# scope.net
KiCad netlist of a schematic drawn in EAGLE
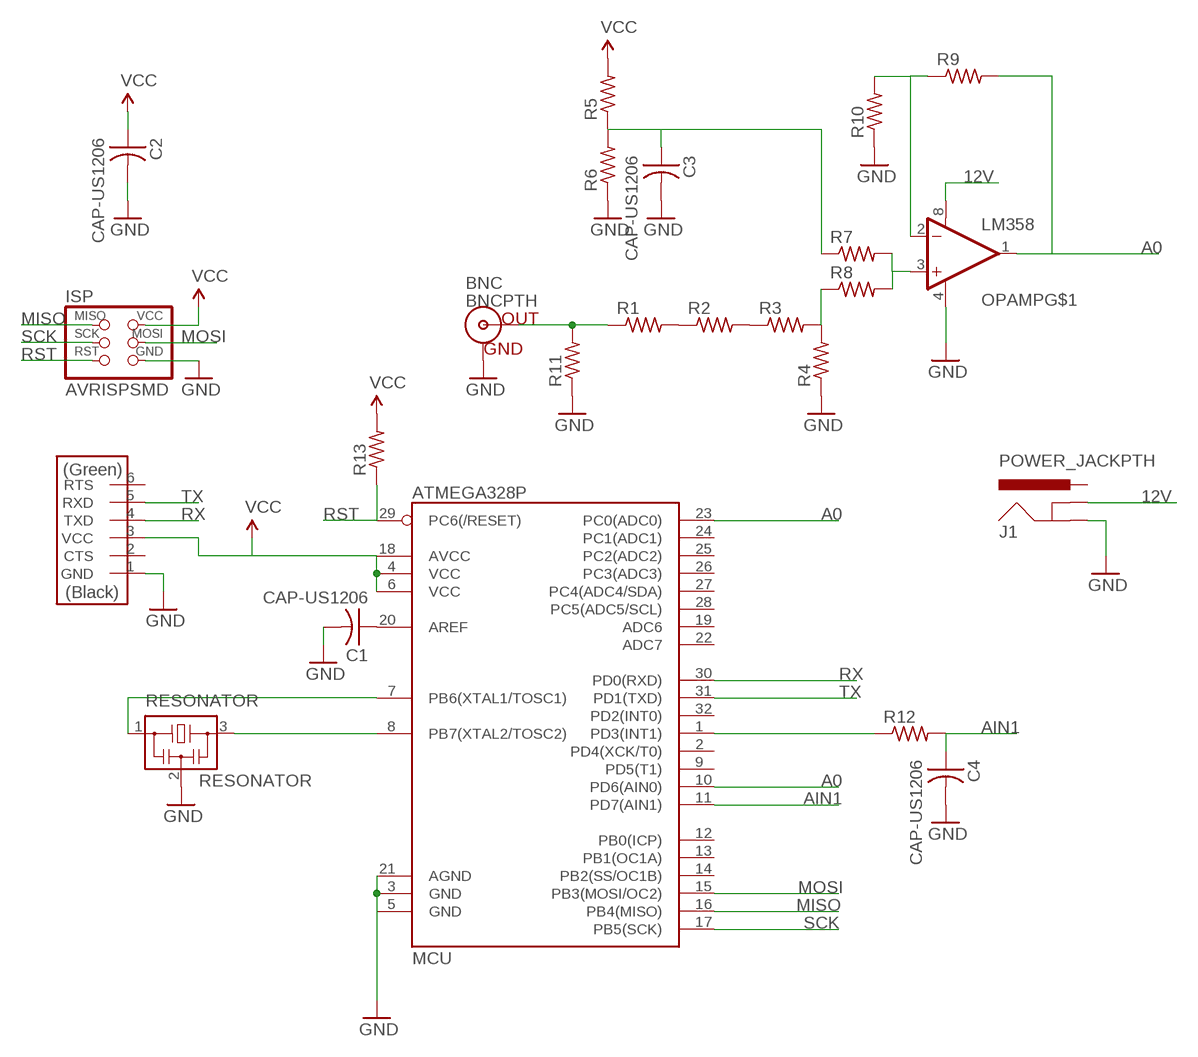
[diagram p0: schematic, sheet 1]

(export (version "E")
  (design (tool "Eeschema 10.0.6"))
  (components
    (comp (ref "BNC")
      (value "BNCPTH")
      (footprint "eagle-import:BNC")
      (libsource (lib "eagle-import") (part "BNCPTH"))
    )
    (comp (ref "C1")
      (value "CAP-US1206")
      (footprint "eagle-import:C1206")
      (libsource (lib "eagle-import") (part "CAP-US1206"))
    )
    (comp (ref "C2")
      (value "CAP-US1206")
      (footprint "eagle-import:C1206")
      (libsource (lib "eagle-import") (part "CAP-US1206"))
    )
    (comp (ref "C3")
      (value "CAP-US1206")
      (footprint "eagle-import:C1206")
      (libsource (lib "eagle-import") (part "CAP-US1206"))
    )
    (comp (ref "C4")
      (value "CAP-US1206")
      (footprint "eagle-import:C1206")
      (libsource (lib "eagle-import") (part "CAP-US1206"))
    )
    (comp (ref "FTDI")
      (value "FTDI-SMD-HEADER")
      (footprint "eagle-import:1X06SMD")
      (libsource (lib "eagle-import") (part "FTDI-SMD-HEADER"))
    )
    (comp (ref "ISP")
      (value "AVRISPSMD")
      (footprint "eagle-import:2X03SMD")
      (libsource (lib "eagle-import") (part "AVRISPSMD"))
    )
    (comp (ref "J1")
      (value "POWER_JACKPTH")
      (footprint "eagle-import:POWER_JACK_PTH")
      (libsource (lib "eagle-import") (part "POWER_JACKPTH"))
    )
    (comp (ref "MCU")
      (value "ATMEGA328P")
      (footprint "eagle-import:TQFP32-08")
      (libsource (lib "eagle-import") (part "ATMEGA328_SMT"))
    )
    (comp (ref "OPAMP")
      (value "LM358")
      (footprint "eagle-import:DIP08")
      (libsource (lib "eagle-import") (part "LM358"))
    )
    (comp (ref "R1")
      (value "RES-US1206")
      (footprint "eagle-import:R1206")
      (libsource (lib "eagle-import") (part "RES-US1206"))
    )
    (comp (ref "R2")
      (value "RES-US1206")
      (footprint "eagle-import:R1206")
      (libsource (lib "eagle-import") (part "RES-US1206"))
    )
    (comp (ref "R3")
      (value "RES-US1206")
      (footprint "eagle-import:R1206")
      (libsource (lib "eagle-import") (part "RES-US1206"))
    )
    (comp (ref "R4")
      (value "RES-US1206")
      (footprint "eagle-import:R1206")
      (libsource (lib "eagle-import") (part "RES-US1206"))
    )
    (comp (ref "R5")
      (value "RES-US1206")
      (footprint "eagle-import:R1206")
      (libsource (lib "eagle-import") (part "RES-US1206"))
    )
    (comp (ref "R6")
      (value "RES-US1206")
      (footprint "eagle-import:R1206")
      (libsource (lib "eagle-import") (part "RES-US1206"))
    )
    (comp (ref "R7")
      (value "RES-US1206")
      (footprint "eagle-import:R1206")
      (libsource (lib "eagle-import") (part "RES-US1206"))
    )
    (comp (ref "R8")
      (value "RES-US1206")
      (footprint "eagle-import:R1206")
      (libsource (lib "eagle-import") (part "RES-US1206"))
    )
    (comp (ref "R9")
      (value "RES-US1206")
      (footprint "eagle-import:R1206")
      (libsource (lib "eagle-import") (part "RES-US1206"))
    )
    (comp (ref "R10")
      (value "RES-US1206")
      (footprint "eagle-import:R1206")
      (libsource (lib "eagle-import") (part "RES-US1206"))
    )
    (comp (ref "R11")
      (value "RES-US1206")
      (footprint "eagle-import:R1206")
      (libsource (lib "eagle-import") (part "RES-US1206"))
    )
    (comp (ref "R12")
      (value "RES-US1206")
      (footprint "eagle-import:R1206")
      (libsource (lib "eagle-import") (part "RES-US1206"))
    )
    (comp (ref "R13")
      (value "RES-US1206")
      (footprint "eagle-import:R1206")
      (libsource (lib "eagle-import") (part "RES-US1206"))
    )
    (comp (ref "RESONATOR")
      (value "RESONATOR")
      (footprint "eagle-import:EFOBM")
      (libsource (lib "eagle-import") (part "RESONATOR"))
    )
  )
  (nets
    (net (code "1") (name "/12V") (class "Default")
      (node (ref "J1") (pin "GNDBREAK") (pinfunction "GNDBREAK_GNDBREAK") (pintype "bidirectional"))
      (node (ref "OPAMP") (pin "8") (pinfunction "V+_8") (pintype "power_in"))
    )
    (net (code "2") (name "/A0") (class "Default")
      (node (ref "MCU") (pin "10") (pinfunction "PD6(AIN0)_10") (pintype "bidirectional"))
      (node (ref "MCU") (pin "23") (pinfunction "PC0(ADC0)_23") (pintype "bidirectional"))
      (node (ref "OPAMP") (pin "1") (pinfunction "OUT_1") (pintype "output"))
      (node (ref "R9") (pin "2") (pinfunction "2_2") (pintype "passive"))
    )
    (net (code "3") (name "/AIN1") (class "Default")
      (node (ref "C4") (pin "1") (pinfunction "1_1") (pintype "passive"))
      (node (ref "MCU") (pin "11") (pinfunction "PD7(AIN1)_11") (pintype "bidirectional"))
      (node (ref "R12") (pin "2") (pinfunction "2_2") (pintype "passive"))
    )
    (net (code "4") (name "/MISO") (class "Default")
      (node (ref "ISP") (pin "1") (pinfunction "MISO_1") (pintype "passive"))
      (node (ref "MCU") (pin "16") (pinfunction "PB4(MISO)_16") (pintype "bidirectional"))
    )
    (net (code "5") (name "/MOSI") (class "Default")
      (node (ref "ISP") (pin "4") (pinfunction "MOSI_4") (pintype "passive"))
      (node (ref "MCU") (pin "15") (pinfunction "PB3(MOSI/OC2)_15") (pintype "bidirectional"))
    )
    (net (code "6") (name "/RST") (class "Default")
      (node (ref "ISP") (pin "5") (pinfunction "RST_5") (pintype "passive"))
      (node (ref "MCU") (pin "29") (pinfunction "PC6(/RESET)_29") (pintype "bidirectional"))
      (node (ref "R13") (pin "1") (pinfunction "1_1") (pintype "passive"))
    )
    (net (code "7") (name "/RX") (class "Default")
      (node (ref "FTDI") (pin "4") (pinfunction "TXD_4") (pintype "bidirectional"))
      (node (ref "MCU") (pin "30") (pinfunction "PD0(RXD)_30") (pintype "bidirectional"))
    )
    (net (code "8") (name "/SCK") (class "Default")
      (node (ref "ISP") (pin "3") (pinfunction "SCK_3") (pintype "passive"))
      (node (ref "MCU") (pin "17") (pinfunction "PB5(SCK)_17") (pintype "bidirectional"))
    )
    (net (code "9") (name "/TX") (class "Default")
      (node (ref "FTDI") (pin "5") (pinfunction "RXD_5") (pintype "bidirectional"))
      (node (ref "MCU") (pin "31") (pinfunction "PD1(TXD)_31") (pintype "bidirectional"))
    )
    (net (code "10") (name "GND") (class "Default")
      (node (ref "BNC") (pin "GND") (pinfunction "GND_GND") (pintype "bidirectional"))
      (node (ref "C1") (pin "2") (pinfunction "2_2") (pintype "passive"))
      (node (ref "C2") (pin "2") (pinfunction "2_2") (pintype "passive"))
      (node (ref "C3") (pin "2") (pinfunction "2_2") (pintype "passive"))
      (node (ref "C4") (pin "2") (pinfunction "2_2") (pintype "passive"))
      (node (ref "FTDI") (pin "1") (pinfunction "GND_1") (pintype "bidirectional"))
      (node (ref "ISP") (pin "6") (pinfunction "GND_6") (pintype "passive"))
      (node (ref "J1") (pin "GND") (pinfunction "GND_GND") (pintype "bidirectional"))
      (node (ref "MCU") (pin "21") (pinfunction "AGND_21") (pintype "bidirectional"))
      (node (ref "MCU") (pin "3") (pinfunction "GND_3") (pintype "bidirectional"))
      (node (ref "MCU") (pin "5") (pinfunction "GND_5") (pintype "bidirectional"))
      (node (ref "OPAMP") (pin "4") (pinfunction "V-_4") (pintype "power_in"))
      (node (ref "R10") (pin "1") (pinfunction "1_1") (pintype "passive"))
      (node (ref "R11") (pin "1") (pinfunction "1_1") (pintype "passive"))
      (node (ref "R4") (pin "1") (pinfunction "1_1") (pintype "passive"))
      (node (ref "R6") (pin "1") (pinfunction "1_1") (pintype "passive"))
      (node (ref "RESONATOR") (pin "2") (pinfunction "2_2") (pintype "passive"))
    )
    (net (code "11") (name "Net-(BNC-OUT)") (class "Default")
      (node (ref "BNC") (pin "S") (pinfunction "OUT_S") (pintype "bidirectional"))
      (node (ref "R1") (pin "1") (pinfunction "1_1") (pintype "passive"))
      (node (ref "R11") (pin "2") (pinfunction "2_2") (pintype "passive"))
    )
    (net (code "12") (name "Net-(C3-Pad1)") (class "Default")
      (node (ref "C3") (pin "1") (pinfunction "1_1") (pintype "passive"))
      (node (ref "R5") (pin "1") (pinfunction "1_1") (pintype "passive"))
      (node (ref "R6") (pin "2") (pinfunction "2_2") (pintype "passive"))
      (node (ref "R7") (pin "1") (pinfunction "1_1") (pintype "passive"))
    )
    (net (code "13") (name "Net-(MCU-AREF)") (class "Default")
      (node (ref "C1") (pin "1") (pinfunction "1_1") (pintype "passive"))
      (node (ref "MCU") (pin "20") (pinfunction "AREF_20") (pintype "bidirectional"))
    )
    (net (code "14") (name "Net-(MCU-PB6(XTAL1{slash}TOSC1))") (class "Default")
      (node (ref "MCU") (pin "7") (pinfunction "PB6(XTAL1/TOSC1)_7") (pintype "bidirectional"))
      (node (ref "RESONATOR") (pin "1") (pinfunction "1_1") (pintype "passive"))
    )
    (net (code "15") (name "Net-(MCU-PB7(XTAL2{slash}TOSC2))") (class "Default")
      (node (ref "MCU") (pin "8") (pinfunction "PB7(XTAL2/TOSC2)_8") (pintype "bidirectional"))
      (node (ref "RESONATOR") (pin "3") (pinfunction "3_3") (pintype "passive"))
    )
    (net (code "16") (name "Net-(MCU-PD3(INT1))") (class "Default")
      (node (ref "MCU") (pin "1") (pinfunction "PD3(INT1)_1") (pintype "bidirectional"))
      (node (ref "R12") (pin "1") (pinfunction "1_1") (pintype "passive"))
    )
    (net (code "17") (name "Net-(OPAMPA-+IN)") (class "Default")
      (node (ref "OPAMP") (pin "3") (pinfunction "+IN_3") (pintype "input"))
      (node (ref "R7") (pin "2") (pinfunction "2_2") (pintype "passive"))
      (node (ref "R8") (pin "2") (pinfunction "2_2") (pintype "passive"))
    )
    (net (code "18") (name "Net-(OPAMPA--IN)") (class "Default")
      (node (ref "OPAMP") (pin "2") (pinfunction "-IN_2") (pintype "input"))
      (node (ref "R10") (pin "2") (pinfunction "2_2") (pintype "passive"))
      (node (ref "R9") (pin "1") (pinfunction "1_1") (pintype "passive"))
    )
    (net (code "19") (name "Net-(R1-Pad2)") (class "Default")
      (node (ref "R1") (pin "2") (pinfunction "2_2") (pintype "passive"))
      (node (ref "R2") (pin "1") (pinfunction "1_1") (pintype "passive"))
    )
    (net (code "20") (name "Net-(R2-Pad2)") (class "Default")
      (node (ref "R2") (pin "2") (pinfunction "2_2") (pintype "passive"))
      (node (ref "R3") (pin "1") (pinfunction "1_1") (pintype "passive"))
    )
    (net (code "21") (name "Net-(R3-Pad2)") (class "Default")
      (node (ref "R3") (pin "2") (pinfunction "2_2") (pintype "passive"))
      (node (ref "R4") (pin "2") (pinfunction "2_2") (pintype "passive"))
      (node (ref "R8") (pin "1") (pinfunction "1_1") (pintype "passive"))
    )
    (net (code "22") (name "VCC") (class "Default")
      (node (ref "C2") (pin "1") (pinfunction "1_1") (pintype "passive"))
      (node (ref "FTDI") (pin "3") (pinfunction "VCC_3") (pintype "bidirectional"))
      (node (ref "ISP") (pin "2") (pinfunction "VCC_2") (pintype "passive"))
      (node (ref "MCU") (pin "18") (pinfunction "AVCC_18") (pintype "bidirectional"))
      (node (ref "MCU") (pin "4") (pinfunction "VCC_4") (pintype "bidirectional"))
      (node (ref "MCU") (pin "6") (pinfunction "VCC_6") (pintype "bidirectional"))
      (node (ref "R13") (pin "2") (pinfunction "2_2") (pintype "passive"))
      (node (ref "R5") (pin "2") (pinfunction "2_2") (pintype "passive"))
    )
    (net (code "23") (name "unconnected-(FTDI-CTS-Pad2)") (class "Default")
      (node (ref "FTDI") (pin "2") (pinfunction "CTS_2") (pintype "bidirectional"))
    )
    (net (code "24") (name "unconnected-(FTDI-RTS-Pad6)") (class "Default")
      (node (ref "FTDI") (pin "6") (pinfunction "RTS_6") (pintype "bidirectional"))
    )
    (net (code "25") (name "unconnected-(J1-PadPWR)") (class "Default")
      (node (ref "J1") (pin "PWR") (pinfunction "PWR_PWR") (pintype "bidirectional"))
    )
    (net (code "26") (name "unconnected-(MCU-ADC6-Pad19)") (class "Default")
      (node (ref "MCU") (pin "19") (pinfunction "ADC6_19") (pintype "bidirectional"))
    )
    (net (code "27") (name "unconnected-(MCU-ADC7-Pad22)") (class "Default")
      (node (ref "MCU") (pin "22") (pinfunction "ADC7_22") (pintype "bidirectional"))
    )
    (net (code "28") (name "unconnected-(MCU-PB0(ICP)-Pad12)") (class "Default")
      (node (ref "MCU") (pin "12") (pinfunction "PB0(ICP)_12") (pintype "bidirectional"))
    )
    (net (code "29") (name "unconnected-(MCU-PB1(OC1A)-Pad13)") (class "Default")
      (node (ref "MCU") (pin "13") (pinfunction "PB1(OC1A)_13") (pintype "bidirectional"))
    )
    (net (code "30") (name "unconnected-(MCU-PB2(SS{slash}OC1B)-Pad14)") (class "Default")
      (node (ref "MCU") (pin "14") (pinfunction "PB2(SS/OC1B)_14") (pintype "bidirectional"))
    )
    (net (code "31") (name "unconnected-(MCU-PC1(ADC1)-Pad24)") (class "Default")
      (node (ref "MCU") (pin "24") (pinfunction "PC1(ADC1)_24") (pintype "bidirectional"))
    )
    (net (code "32") (name "unconnected-(MCU-PC2(ADC2)-Pad25)") (class "Default")
      (node (ref "MCU") (pin "25") (pinfunction "PC2(ADC2)_25") (pintype "bidirectional"))
    )
    (net (code "33") (name "unconnected-(MCU-PC3(ADC3)-Pad26)") (class "Default")
      (node (ref "MCU") (pin "26") (pinfunction "PC3(ADC3)_26") (pintype "bidirectional"))
    )
    (net (code "34") (name "unconnected-(MCU-PC4(ADC4{slash}SDA)-Pad27)") (class "Default")
      (node (ref "MCU") (pin "27") (pinfunction "PC4(ADC4/SDA)_27") (pintype "bidirectional"))
    )
    (net (code "35") (name "unconnected-(MCU-PC5(ADC5{slash}SCL)-Pad28)") (class "Default")
      (node (ref "MCU") (pin "28") (pinfunction "PC5(ADC5/SCL)_28") (pintype "bidirectional"))
    )
    (net (code "36") (name "unconnected-(MCU-PD2(INT0)-Pad32)") (class "Default")
      (node (ref "MCU") (pin "32") (pinfunction "PD2(INT0)_32") (pintype "bidirectional"))
    )
    (net (code "37") (name "unconnected-(MCU-PD4(XCK{slash}T0)-Pad2)") (class "Default")
      (node (ref "MCU") (pin "2") (pinfunction "PD4(XCK/T0)_2") (pintype "bidirectional"))
    )
    (net (code "38") (name "unconnected-(MCU-PD5(T1)-Pad9)") (class "Default")
      (node (ref "MCU") (pin "9") (pinfunction "PD5(T1)_9") (pintype "bidirectional"))
    )
  )
)
